# ds1307_ek_narrow.net
KiCad netlist of a schematic drawn in EAGLE
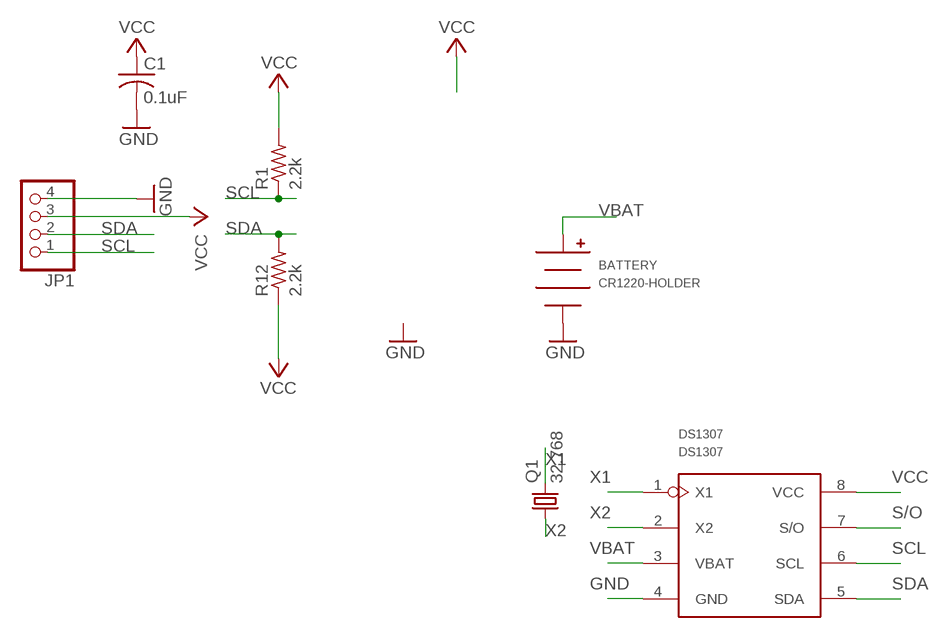
[diagram p0: schematic, sheet 1]

(export (version "E")
  (design (tool "Eeschema 10.0.6"))
  (components
    (comp (ref "BATTERY")
      (value "CR1220-HOLDER")
      (footprint "eagle-import:HARWIN-CR1220")
      (libsource (lib "eagle-import") (part "CR1220-HOLDER"))
    )
    (comp (ref "C1")
      (value "0.1uF")
      (footprint "eagle-import:C0805")
      (libsource (lib "eagle-import") (part "C-USC0805"))
    )
    (comp (ref "DS1307")
      (value "DS1307")
      (footprint "eagle-import:SO08")
      (libsource (lib "eagle-import") (part "DS1307"))
    )
    (comp (ref "JP1")
      (value "PINHD-1X4")
      (footprint "eagle-import:1X04")
      (libsource (lib "eagle-import") (part "PINHD-1X4"))
    )
    (comp (ref "Q1")
      (value "32.768")
      (footprint "eagle-import:TC38H")
      (libsource (lib "eagle-import") (part "CRYTALTC38H"))
    )
    (comp (ref "R1")
      (value "2.2k")
      (footprint "eagle-import:R0805")
      (libsource (lib "eagle-import") (part "R-US_R0805"))
    )
    (comp (ref "R12")
      (value "2.2k")
      (footprint "eagle-import:R0805")
      (libsource (lib "eagle-import") (part "R-US_R0805"))
    )
  )
  (nets
    (net (code "1") (name "/SCL") (class "Default")
      (node (ref "DS1307") (pin "6") (pinfunction "SCL_6") (pintype "bidirectional"))
      (node (ref "JP1") (pin "1") (pinfunction "1_1") (pintype "passive"))
      (node (ref "R1") (pin "1") (pinfunction "1_1") (pintype "passive"))
    )
    (net (code "2") (name "/SDA") (class "Default")
      (node (ref "DS1307") (pin "5") (pinfunction "SDA_5") (pintype "bidirectional"))
      (node (ref "JP1") (pin "2") (pinfunction "2_2") (pintype "passive"))
      (node (ref "R12") (pin "2") (pinfunction "2_2") (pintype "passive"))
    )
    (net (code "3") (name "/S{slash}O") (class "Default")
      (node (ref "DS1307") (pin "7") (pinfunction "S/O_7") (pintype "bidirectional"))
    )
    (net (code "4") (name "/VBAT") (class "Default")
      (node (ref "BATTERY") (pin "POS") (pinfunction "POS_POS") (pintype "bidirectional"))
      (node (ref "DS1307") (pin "3") (pinfunction "VBAT_3") (pintype "bidirectional"))
    )
    (net (code "5") (name "/X1") (class "Default")
      (node (ref "DS1307") (pin "1") (pinfunction "X1_1") (pintype "bidirectional"))
      (node (ref "Q1") (pin "2") (pinfunction "2_2") (pintype "passive"))
    )
    (net (code "6") (name "/X2") (class "Default")
      (node (ref "DS1307") (pin "2") (pinfunction "X2_2") (pintype "bidirectional"))
      (node (ref "Q1") (pin "1") (pinfunction "1_1") (pintype "passive"))
    )
    (net (code "7") (name "GND") (class "Default")
      (node (ref "BATTERY") (pin "NEG") (pinfunction "NEG_NEG") (pintype "bidirectional"))
      (node (ref "C1") (pin "2") (pinfunction "2_2") (pintype "passive"))
      (node (ref "DS1307") (pin "4") (pinfunction "GND_4") (pintype "bidirectional"))
      (node (ref "JP1") (pin "4") (pinfunction "4_4") (pintype "passive"))
    )
    (net (code "8") (name "VCC") (class "Default")
      (node (ref "C1") (pin "1") (pinfunction "1_1") (pintype "passive"))
      (node (ref "DS1307") (pin "8") (pinfunction "VCC_8") (pintype "bidirectional"))
      (node (ref "JP1") (pin "3") (pinfunction "3_3") (pintype "passive"))
      (node (ref "R1") (pin "2") (pinfunction "2_2") (pintype "passive"))
      (node (ref "R12") (pin "1") (pinfunction "1_1") (pintype "passive"))
    )
  )
)
